# NguyenLy.net
KiCad netlist of a schematic drawn in Altium Designer
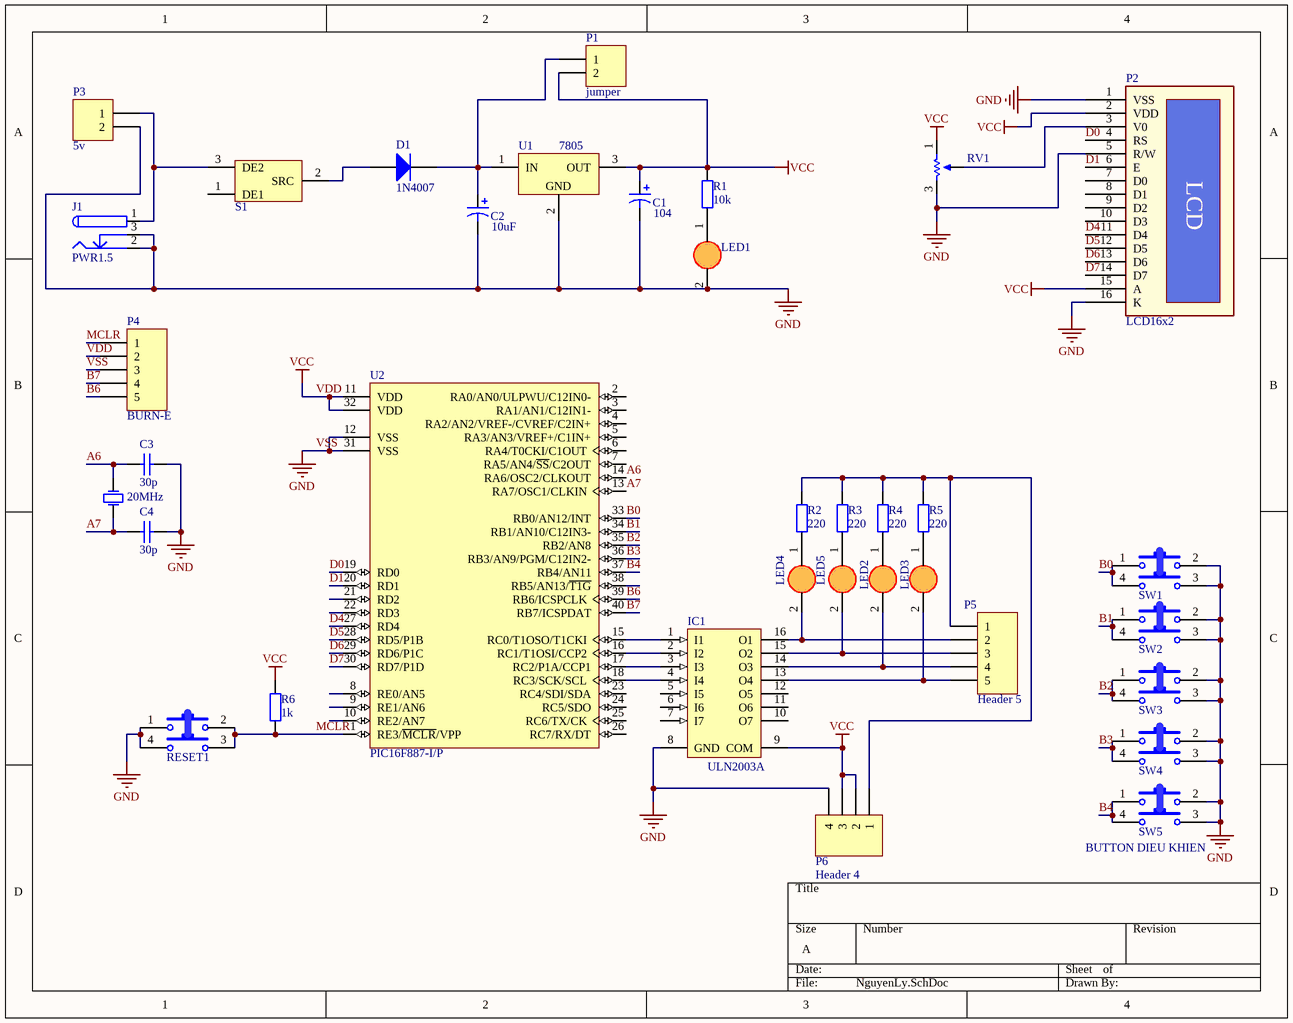
[diagram p0: NguyenLy.SchDoc]

(export (version "E")
  (design (tool "Eeschema 10.0.6"))
  (components
    (comp (ref "C1")
      (value "104")
      (footprint "C3MM")
      (description "Polarized Capacitor (Axial)")
      (fields (field (name "PUBLISHER") "Altium Limited"))
      (libsource (lib "NBBLib 14-03-2012") (part "Cap Pol 3mm"))
    )
    (comp (ref "C2")
      (value "10uF")
      (footprint "C3MM")
      (description "Polarized Capacitor (Axial)")
      (fields (field (name "PUBLISHER") "Altium Limited"))
      (libsource (lib "NBBLib 14-03-2012") (part "Cap Pol 3mm"))
    )
    (comp (ref "C3")
      (value "30p")
      (footprint "Tu-ceramic")
      (description "Capacitor")
      (fields (field (name "Comment") "Capacitor Ceramic") (field (name "PUBLISHER") "Altium Limited"))
      (libsource (lib "NBBLib 14-03-2012") (part "CapDecop"))
    )
    (comp (ref "C4")
      (value "30p")
      (footprint "Tu-ceramic")
      (description "Capacitor")
      (fields (field (name "Comment") "Capacitor Ceramic") (field (name "PUBLISHER") "Altium Limited"))
      (libsource (lib "NBBLib 14-03-2012") (part "CapDecop"))
    )
    (comp (ref "D1")
      (value "1N4007")
      (footprint "DIODE/POW/1A")
      (description "Diode Power")
      (fields (field (name "PUBLISHER") "Altium Limited"))
      (libsource (lib "NBBLib 14-03-2012") (part "Diode Power"))
    )
    (comp (ref "IC1")
      (value "ULN2003A")
      (footprint "DIP16/W0.3")
      (description "High-Voltage, High-Current Darlington Array")
      (fields (field (name "PUBLISHER") "Altium Limited"))
      (libsource (lib "syhaunguyen") (part "ULN2003A"))
    )
    (comp (ref "J1")
      (value "PWR1.5")
      (footprint "PW-J-1MM")
      (description "Low Voltage Power Supply Connector")
      (fields (field (name "PUBLISHER") "Altium Limited"))
      (libsource (lib "NBBLib 14-03-2012") (part "PWR1.5"))
    )
    (comp (ref "LED1")
      (value "LED5")
      (footprint "LED5MM")
      (description "LED 5mm")
      (libsource (lib "NBBLib 14-03-2012") (part "LED 5mm"))
    )
    (comp (ref "LED2")
      (value "LED5")
      (footprint "LED5MM")
      (description "LED 5mm")
      (libsource (lib "NBBLib 14-03-2012") (part "LED 5mm"))
    )
    (comp (ref "LED3")
      (value "LED5")
      (footprint "LED5MM")
      (description "LED 5mm")
      (libsource (lib "NBBLib 14-03-2012") (part "LED 5mm"))
    )
    (comp (ref "LED4")
      (value "LED5")
      (footprint "LED5MM")
      (description "LED 5mm")
      (libsource (lib "NBBLib 14-03-2012") (part "LED 5mm"))
    )
    (comp (ref "LED5")
      (value "LED5")
      (footprint "LED5MM")
      (description "LED 5mm")
      (libsource (lib "NBBLib 14-03-2012") (part "LED 5mm"))
    )
    (comp (ref "P1")
      (value "jumper")
      (footprint "HDR1X2")
      (description "Header, 2-Pin")
      (fields (field (name "PUBLISHER") "Altium Limited"))
      (libsource (lib "NBBLib 14-03-2012") (part "Header 2"))
    )
    (comp (ref "P2")
      (value "LCD16x2")
      (footprint "HDR1X16")
      (libsource (lib "NBBLib 14-03-2012") (part "LCD Text"))
    )
    (comp (ref "P3")
      (value "5v")
      (footprint "HDR1X2")
      (description "Header, 2-Pin")
      (fields (field (name "PUBLISHER") "Altium Limited"))
      (libsource (lib "") (part "Header 2_1"))
    )
    (comp (ref "P4")
      (value "BURN-E")
      (footprint "HDR1X5")
      (description "Header, 5-Pin")
      (fields (field (name "PUBLISHER") "Altium Limited"))
      (libsource (lib "NBBLib 14-03-2012") (part "Header 5"))
    )
    (comp (ref "P5")
      (value "Header 5")
      (footprint "HDR1X5")
      (description "Header, 5-Pin")
      (fields (field (name "PUBLISHER") "Altium Limited"))
      (libsource (lib "NBBLib 14-03-2012") (part "Header 5"))
    )
    (comp (ref "P6")
      (value "Header 4")
      (footprint "HDR1X4")
      (description "Header, 4-Pin")
      (fields (field (name "PUBLISHER") "Altium Limited"))
      (libsource (lib "NBBLib 14-03-2012") (part "Header 4"))
    )
    (comp (ref "R1")
      (value "10k")
      (footprint "DIEN TRO 1/4 W")
      (description "Resistor")
      (fields (field (name "Comment") "R0.4W") (field (name "PUBLISHER") "Altium Limited"))
      (libsource (lib "NBBLib 14-03-2012") (part "Res 1/4 W"))
    )
    (comp (ref "R2")
      (value "220")
      (footprint "DIEN TRO 1/4 W")
      (description "Resistor")
      (fields (field (name "Comment") "R0.4W") (field (name "PUBLISHER") "Altium Limited"))
      (libsource (lib "NBBLib 14-03-2012") (part "Res 1/4 W"))
    )
    (comp (ref "R3")
      (value "220")
      (footprint "DIEN TRO 1/4 W")
      (description "Resistor")
      (fields (field (name "Comment") "R0.4W") (field (name "PUBLISHER") "Altium Limited"))
      (libsource (lib "NBBLib 14-03-2012") (part "Res 1/4 W"))
    )
    (comp (ref "R4")
      (value "220")
      (footprint "DIEN TRO 1/4 W")
      (description "Resistor")
      (fields (field (name "Comment") "R0.4W") (field (name "PUBLISHER") "Altium Limited"))
      (libsource (lib "NBBLib 14-03-2012") (part "Res 1/4 W"))
    )
    (comp (ref "R5")
      (value "220")
      (footprint "DIEN TRO 1/4 W")
      (description "Resistor")
      (fields (field (name "Comment") "R0.4W") (field (name "PUBLISHER") "Altium Limited"))
      (libsource (lib "NBBLib 14-03-2012") (part "Res 1/4 W"))
    )
    (comp (ref "R6")
      (value "1k")
      (footprint "DIEN TRO 1/4 W")
      (description "Resistor")
      (fields (field (name "Comment") "R0.4W") (field (name "PUBLISHER") "Altium Limited"))
      (libsource (lib "") (part "Res 1/4 W_1"))
    )
    (comp (ref "RESET1")
      (value "SW-4P-S")
      (footprint "SW-4P-S")
      (description "Switch Small 4 Pin")
      (fields (field (name "PUBLISHER") "Altium Limited"))
      (libsource (lib "NBBLib 14-03-2012") (part "SW-4PIN-SMALL"))
    )
    (comp (ref "RV1")
      (value "RV20K")
      (footprint "RVAR10K")
      (description "Variable Resistor")
      (fields (field (name "PUBLISHER") "Altium Limited"))
      (libsource (lib "NBBLib 14-03-2012") (part "Variable Resistor"))
    )
    (comp (ref "S1")
      (value "Switch")
      (footprint "Switch")
      (libsource (lib "NBBLib 14-03-2012") (part "Switch"))
    )
    (comp (ref "SW1")
      (value "SW-4P-S")
      (footprint "SW-4P-S")
      (description "Switch Small 4 Pin")
      (fields (field (name "PUBLISHER") "Altium Limited"))
      (libsource (lib "NBBLib 14-03-2012") (part "SW-4PIN-SMALL"))
    )
    (comp (ref "SW2")
      (value "SW-4P-S")
      (footprint "SW-4P-S")
      (description "Switch Small 4 Pin")
      (fields (field (name "PUBLISHER") "Altium Limited"))
      (libsource (lib "NBBLib 14-03-2012") (part "SW-4PIN-SMALL"))
    )
    (comp (ref "SW3")
      (value "SW-4P-S")
      (footprint "SW-4P-S")
      (description "Switch Small 4 Pin")
      (fields (field (name "PUBLISHER") "Altium Limited"))
      (libsource (lib "NBBLib 14-03-2012") (part "SW-4PIN-SMALL"))
    )
    (comp (ref "SW4")
      (value "SW-4P-S")
      (footprint "SW-4P-S")
      (description "Switch Small 4 Pin")
      (fields (field (name "PUBLISHER") "Altium Limited"))
      (libsource (lib "NBBLib 14-03-2012") (part "SW-4PIN-SMALL"))
    )
    (comp (ref "SW5")
      (value "SW-4P-S")
      (footprint "SW-4P-S")
      (description "Switch Small 4 Pin")
      (fields (field (name "PUBLISHER") "Altium Limited"))
      (libsource (lib "NBBLib 14-03-2012") (part "SW-4PIN-SMALL"))
    )
    (comp (ref "U1")
      (value "7805")
      (footprint "HDR1x3 BIG")
      (description "Positive Voltage Regulator")
      (fields (field (name "PUBLISHER") "Altium Limited"))
      (libsource (lib "NBBLib 14-03-2012") (part "7809"))
    )
    (comp (ref "U2")
      (value "PIC16F887-I/P")
      (footprint "PDIP600-P40")
      (fields (field (name "PUBLISHER") "Altium Limited"))
      (libsource (lib "Microchip Microcontroller 8-Bit PIC16") (part "PIC16F887-I/P"))
    )
    (comp (ref "Y1")
      (value "20MHz")
      (footprint "XTAL")
      (description "Crystal Oscillator")
      (fields (field (name "PUBLISHER") "Altium Limited"))
      (libsource (lib "NBBLib 14-03-2012") (part "XTAL"))
    )
  )
  (nets
    (net (code "1") (name "/A6") (class "Default")
      (node (ref "C3") (pin "1") (pinfunction "1_1") (pintype "passive"))
      (node (ref "U2") (pin "14") (pinfunction "RA6/OSC2/CLKOUT_14") (pintype "bidirectional"))
      (node (ref "Y1") (pin "2") (pinfunction "OSC2_2") (pintype "passive"))
    )
    (net (code "2") (name "/A7") (class "Default")
      (node (ref "C4") (pin "1") (pinfunction "1_1") (pintype "passive"))
      (node (ref "U2") (pin "13") (pinfunction "RA7/OSC1/CLKIN_13") (pintype "bidirectional"))
      (node (ref "Y1") (pin "1") (pinfunction "OSC1_1") (pintype "passive"))
    )
    (net (code "3") (name "/B0") (class "Default")
      (node (ref "SW1") (pin "1") (pinfunction "1_1") (pintype "passive"))
      (node (ref "SW1") (pin "4") (pinfunction "4_4") (pintype "passive"))
      (node (ref "U2") (pin "33") (pinfunction "RB0/AN12/INT_33") (pintype "bidirectional"))
    )
    (net (code "4") (name "/B1") (class "Default")
      (node (ref "SW2") (pin "1") (pinfunction "1_1") (pintype "passive"))
      (node (ref "SW2") (pin "4") (pinfunction "4_4") (pintype "passive"))
      (node (ref "U2") (pin "34") (pinfunction "RB1/AN10/C12IN3-_34") (pintype "bidirectional"))
    )
    (net (code "5") (name "/B2") (class "Default")
      (node (ref "SW3") (pin "1") (pinfunction "1_1") (pintype "passive"))
      (node (ref "SW3") (pin "4") (pinfunction "4_4") (pintype "passive"))
      (node (ref "U2") (pin "35") (pinfunction "RB2/AN8_35") (pintype "bidirectional"))
    )
    (net (code "6") (name "/B3") (class "Default")
      (node (ref "SW4") (pin "1") (pinfunction "1_1") (pintype "passive"))
      (node (ref "SW4") (pin "4") (pinfunction "4_4") (pintype "passive"))
      (node (ref "U2") (pin "36") (pinfunction "RB3/AN9/PGM/C12IN2-_36") (pintype "bidirectional"))
    )
    (net (code "7") (name "/B4") (class "Default")
      (node (ref "SW5") (pin "1") (pinfunction "1_1") (pintype "passive"))
      (node (ref "SW5") (pin "4") (pinfunction "4_4") (pintype "passive"))
      (node (ref "U2") (pin "37") (pinfunction "RB4/AN11_37") (pintype "bidirectional"))
    )
    (net (code "8") (name "/B6") (class "Default")
      (node (ref "P4") (pin "5") (pinfunction "5_5") (pintype "passive"))
      (node (ref "U2") (pin "39") (pinfunction "RB6/ICSPCLK_39") (pintype "bidirectional"))
    )
    (net (code "9") (name "/B7") (class "Default")
      (node (ref "P4") (pin "4") (pinfunction "4_4") (pintype "passive"))
      (node (ref "U2") (pin "40") (pinfunction "RB7/ICSPDAT_40") (pintype "bidirectional"))
    )
    (net (code "10") (name "/D0") (class "Default")
      (node (ref "P2") (pin "4") (pinfunction "RS_4") (pintype "passive"))
      (node (ref "U2") (pin "19") (pinfunction "RD0_19") (pintype "bidirectional"))
    )
    (net (code "11") (name "/D1") (class "Default")
      (node (ref "P2") (pin "6") (pinfunction "E_6") (pintype "passive"))
      (node (ref "U2") (pin "20") (pinfunction "RD1_20") (pintype "bidirectional"))
    )
    (net (code "12") (name "/D4") (class "Default")
      (node (ref "P2") (pin "11") (pinfunction "D4_11") (pintype "passive"))
      (node (ref "U2") (pin "27") (pinfunction "RD4_27") (pintype "bidirectional"))
    )
    (net (code "13") (name "/D5") (class "Default")
      (node (ref "P2") (pin "12") (pinfunction "D5_12") (pintype "passive"))
      (node (ref "U2") (pin "28") (pinfunction "RD5/P1B_28") (pintype "bidirectional"))
    )
    (net (code "14") (name "/D6") (class "Default")
      (node (ref "P2") (pin "13") (pinfunction "D6_13") (pintype "passive"))
      (node (ref "U2") (pin "29") (pinfunction "RD6/P1C_29") (pintype "bidirectional"))
    )
    (net (code "15") (name "/D7") (class "Default")
      (node (ref "P2") (pin "14") (pinfunction "D7_14") (pintype "passive"))
      (node (ref "U2") (pin "30") (pinfunction "RD7/P1D_30") (pintype "bidirectional"))
    )
    (net (code "16") (name "/MCLR") (class "Default")
      (node (ref "P4") (pin "1") (pinfunction "1_1") (pintype "passive"))
      (node (ref "R6") (pin "2") (pinfunction "2_2") (pintype "passive"))
      (node (ref "RESET1") (pin "2") (pinfunction "2_2") (pintype "passive"))
      (node (ref "RESET1") (pin "3") (pinfunction "3_3") (pintype "passive"))
      (node (ref "U2") (pin "1") (pinfunction "RE3/~{MCLR}/VPP_1") (pintype "bidirectional"))
    )
    (net (code "17") (name "GND") (class "Default")
      (node (ref "C1") (pin "2") (pinfunction "2_2") (pintype "passive"))
      (node (ref "C2") (pin "2") (pinfunction "2_2") (pintype "passive"))
      (node (ref "C3") (pin "2") (pinfunction "2_2") (pintype "passive"))
      (node (ref "C4") (pin "2") (pinfunction "2_2") (pintype "passive"))
      (node (ref "IC1") (pin "8") (pinfunction "GND_8") (pintype "power_in"))
      (node (ref "J1") (pin "2") (pinfunction "2_2") (pintype "power_in"))
      (node (ref "J1") (pin "3") (pinfunction "3_3") (pintype "power_in"))
      (node (ref "LED1") (pin "2") (pinfunction "K_2") (pintype "passive"))
      (node (ref "P2") (pin "1") (pinfunction "VSS_1") (pintype "passive"))
      (node (ref "P2") (pin "16") (pinfunction "K_16") (pintype "passive"))
      (node (ref "P2") (pin "5") (pinfunction "R/W_5") (pintype "passive"))
      (node (ref "P3") (pin "2") (pinfunction "2_2") (pintype "passive"))
      (node (ref "P4") (pin "3") (pinfunction "3_3") (pintype "passive"))
      (node (ref "P6") (pin "4") (pinfunction "4_4") (pintype "passive"))
      (node (ref "RESET1") (pin "1") (pinfunction "1_1") (pintype "passive"))
      (node (ref "RESET1") (pin "4") (pinfunction "4_4") (pintype "passive"))
      (node (ref "RV1") (pin "3") (pinfunction "3_3") (pintype "passive"))
      (node (ref "SW1") (pin "2") (pinfunction "2_2") (pintype "passive"))
      (node (ref "SW1") (pin "3") (pinfunction "3_3") (pintype "passive"))
      (node (ref "SW2") (pin "2") (pinfunction "2_2") (pintype "passive"))
      (node (ref "SW2") (pin "3") (pinfunction "3_3") (pintype "passive"))
      (node (ref "SW3") (pin "2") (pinfunction "2_2") (pintype "passive"))
      (node (ref "SW3") (pin "3") (pinfunction "3_3") (pintype "passive"))
      (node (ref "SW4") (pin "2") (pinfunction "2_2") (pintype "passive"))
      (node (ref "SW4") (pin "3") (pinfunction "3_3") (pintype "passive"))
      (node (ref "SW5") (pin "2") (pinfunction "2_2") (pintype "passive"))
      (node (ref "SW5") (pin "3") (pinfunction "3_3") (pintype "passive"))
      (node (ref "U1") (pin "2") (pinfunction "GND_2") (pintype "power_in"))
      (node (ref "U2") (pin "12") (pinfunction "VSS_12") (pintype "power_in"))
      (node (ref "U2") (pin "31") (pinfunction "VSS_31") (pintype "power_in"))
    )
    (net (code "18") (name "Net-(D1-A)") (class "Default")
      (node (ref "D1") (pin "1") (pinfunction "A_1") (pintype "passive"))
      (node (ref "S1") (pin "2") (pinfunction "SRC_2") (pintype "passive"))
    )
    (net (code "19") (name "Net-(D1-K)") (class "Default")
      (node (ref "C2") (pin "1") (pinfunction "1_1") (pintype "passive"))
      (node (ref "D1") (pin "2") (pinfunction "K_2") (pintype "passive"))
      (node (ref "P1") (pin "1") (pinfunction "1_1") (pintype "passive"))
      (node (ref "U1") (pin "1") (pinfunction "IN_1") (pintype "power_in"))
    )
    (net (code "20") (name "Net-(IC1-I1)") (class "Default")
      (node (ref "IC1") (pin "1") (pinfunction "I1_1") (pintype "input"))
      (node (ref "U2") (pin "15") (pinfunction "RC0/T1OSO/T1CKI_15") (pintype "bidirectional"))
    )
    (net (code "21") (name "Net-(IC1-I2)") (class "Default")
      (node (ref "IC1") (pin "2") (pinfunction "I2_2") (pintype "input"))
      (node (ref "U2") (pin "16") (pinfunction "RC1/T1OSI/CCP2_16") (pintype "bidirectional"))
    )
    (net (code "22") (name "Net-(IC1-I3)") (class "Default")
      (node (ref "IC1") (pin "3") (pinfunction "I3_3") (pintype "input"))
      (node (ref "U2") (pin "17") (pinfunction "RC2/P1A/CCP1_17") (pintype "bidirectional"))
    )
    (net (code "23") (name "Net-(IC1-I4)") (class "Default")
      (node (ref "IC1") (pin "4") (pinfunction "I4_4") (pintype "input"))
      (node (ref "U2") (pin "18") (pinfunction "RC3/SCK/SCL_18") (pintype "bidirectional"))
    )
    (net (code "24") (name "Net-(IC1-O1)") (class "Default")
      (node (ref "IC1") (pin "16") (pinfunction "O1_16") (pintype "open_collector"))
      (node (ref "LED4") (pin "2") (pinfunction "K_2") (pintype "passive"))
      (node (ref "P5") (pin "2") (pinfunction "2_2") (pintype "passive"))
    )
    (net (code "25") (name "Net-(IC1-O2)") (class "Default")
      (node (ref "IC1") (pin "15") (pinfunction "O2_15") (pintype "open_collector"))
      (node (ref "LED5") (pin "2") (pinfunction "K_2") (pintype "passive"))
      (node (ref "P5") (pin "3") (pinfunction "3_3") (pintype "passive"))
    )
    (net (code "26") (name "Net-(IC1-O3)") (class "Default")
      (node (ref "IC1") (pin "14") (pinfunction "O3_14") (pintype "open_collector"))
      (node (ref "LED2") (pin "2") (pinfunction "K_2") (pintype "passive"))
      (node (ref "P5") (pin "4") (pinfunction "4_4") (pintype "passive"))
    )
    (net (code "27") (name "Net-(IC1-O4)") (class "Default")
      (node (ref "IC1") (pin "13") (pinfunction "O4_13") (pintype "open_collector"))
      (node (ref "LED3") (pin "2") (pinfunction "K_2") (pintype "passive"))
      (node (ref "P5") (pin "5") (pinfunction "5_5") (pintype "passive"))
    )
    (net (code "28") (name "Net-(LED1-A)") (class "Default")
      (node (ref "LED1") (pin "1") (pinfunction "A_1") (pintype "passive"))
      (node (ref "R1") (pin "1") (pinfunction "1_1") (pintype "passive"))
    )
    (net (code "29") (name "Net-(LED2-A)") (class "Default")
      (node (ref "LED2") (pin "1") (pinfunction "A_1") (pintype "passive"))
      (node (ref "R4") (pin "1") (pinfunction "1_1") (pintype "passive"))
    )
    (net (code "30") (name "Net-(LED3-A)") (class "Default")
      (node (ref "LED3") (pin "1") (pinfunction "A_1") (pintype "passive"))
      (node (ref "R5") (pin "1") (pinfunction "1_1") (pintype "passive"))
    )
    (net (code "31") (name "Net-(LED4-A)") (class "Default")
      (node (ref "LED4") (pin "1") (pinfunction "A_1") (pintype "passive"))
      (node (ref "R2") (pin "1") (pinfunction "1_1") (pintype "passive"))
    )
    (net (code "32") (name "Net-(LED5-A)") (class "Default")
      (node (ref "LED5") (pin "1") (pinfunction "A_1") (pintype "passive"))
      (node (ref "R3") (pin "1") (pinfunction "1_1") (pintype "passive"))
    )
    (net (code "33") (name "Net-(P2-V0)") (class "Default")
      (node (ref "P2") (pin "3") (pinfunction "V0_3") (pintype "passive"))
      (node (ref "RV1") (pin "2") (pinfunction "2_2") (pintype "passive"))
    )
    (net (code "34") (name "Net-(P5-Pad1)") (class "Default")
      (node (ref "P5") (pin "1") (pinfunction "1_1") (pintype "passive"))
      (node (ref "P6") (pin "1") (pinfunction "1_1") (pintype "passive"))
      (node (ref "R2") (pin "2") (pinfunction "2_2") (pintype "passive"))
      (node (ref "R3") (pin "2") (pinfunction "2_2") (pintype "passive"))
      (node (ref "R4") (pin "2") (pinfunction "2_2") (pintype "passive"))
      (node (ref "R5") (pin "2") (pinfunction "2_2") (pintype "passive"))
    )
    (net (code "35") (name "Net-(S1-DE2)") (class "Default")
      (node (ref "J1") (pin "1") (pinfunction "1_1") (pintype "power_in"))
      (node (ref "P3") (pin "1") (pinfunction "1_1") (pintype "passive"))
      (node (ref "S1") (pin "3") (pinfunction "DE2_3") (pintype "passive"))
    )
    (net (code "36") (name "VCC") (class "Default")
      (node (ref "C1") (pin "1") (pinfunction "1_1") (pintype "passive"))
      (node (ref "IC1") (pin "9") (pinfunction "COM_9") (pintype "passive"))
      (node (ref "P1") (pin "2") (pinfunction "2_2") (pintype "passive"))
      (node (ref "P2") (pin "15") (pinfunction "A_15") (pintype "passive"))
      (node (ref "P2") (pin "2") (pinfunction "VDD_2") (pintype "passive"))
      (node (ref "P4") (pin "2") (pinfunction "2_2") (pintype "passive"))
      (node (ref "P6") (pin "2") (pinfunction "2_2") (pintype "passive"))
      (node (ref "P6") (pin "3") (pinfunction "3_3") (pintype "passive"))
      (node (ref "R1") (pin "2") (pinfunction "2_2") (pintype "passive"))
      (node (ref "R6") (pin "1") (pinfunction "1_1") (pintype "passive"))
      (node (ref "RV1") (pin "1") (pinfunction "1_1") (pintype "passive"))
      (node (ref "U1") (pin "3") (pinfunction "OUT_3") (pintype "power_in"))
      (node (ref "U2") (pin "11") (pinfunction "VDD_11") (pintype "power_in"))
      (node (ref "U2") (pin "32") (pinfunction "VDD_32") (pintype "power_in"))
    )
    (net (code "37") (name "unconnected-(IC1-I5-Pad5)") (class "Default")
      (node (ref "IC1") (pin "5") (pinfunction "I5_5") (pintype "input"))
    )
    (net (code "38") (name "unconnected-(IC1-I6-Pad6)") (class "Default")
      (node (ref "IC1") (pin "6") (pinfunction "I6_6") (pintype "input"))
    )
    (net (code "39") (name "unconnected-(IC1-I7-Pad7)") (class "Default")
      (node (ref "IC1") (pin "7") (pinfunction "I7_7") (pintype "input"))
    )
    (net (code "40") (name "unconnected-(IC1-O5-Pad12)") (class "Default")
      (node (ref "IC1") (pin "12") (pinfunction "O5_12") (pintype "open_collector"))
    )
    (net (code "41") (name "unconnected-(IC1-O6-Pad11)") (class "Default")
      (node (ref "IC1") (pin "11") (pinfunction "O6_11") (pintype "open_collector"))
    )
    (net (code "42") (name "unconnected-(IC1-O7-Pad10)") (class "Default")
      (node (ref "IC1") (pin "10") (pinfunction "O7_10") (pintype "open_collector"))
    )
    (net (code "43") (name "unconnected-(P2-D0-Pad7)") (class "Default")
      (node (ref "P2") (pin "7") (pinfunction "D0_7") (pintype "passive"))
    )
    (net (code "44") (name "unconnected-(P2-D1-Pad8)") (class "Default")
      (node (ref "P2") (pin "8") (pinfunction "D1_8") (pintype "passive"))
    )
    (net (code "45") (name "unconnected-(P2-D2-Pad9)") (class "Default")
      (node (ref "P2") (pin "9") (pinfunction "D2_9") (pintype "passive"))
    )
    (net (code "46") (name "unconnected-(P2-D3-Pad10)") (class "Default")
      (node (ref "P2") (pin "10") (pinfunction "D3_10") (pintype "passive"))
    )
    (net (code "47") (name "unconnected-(S1-DE1-Pad1)") (class "Default")
      (node (ref "S1") (pin "1") (pinfunction "DE1_1") (pintype "passive"))
    )
    (net (code "48") (name "unconnected-(S1-Pad4)") (class "Default")
      (node (ref "S1") (pin "4") (pinfunction "4_4") (pintype "passive"))
    )
    (net (code "49") (name "unconnected-(S1-Pad5)") (class "Default")
      (node (ref "S1") (pin "5") (pinfunction "5_5") (pintype "passive"))
    )
    (net (code "50") (name "unconnected-(U2-RA0{slash}AN0{slash}ULPWU{slash}C12IN0--Pad2)") (class "Default")
      (node (ref "U2") (pin "2") (pinfunction "RA0/AN0/ULPWU/C12IN0-_2") (pintype "bidirectional"))
    )
    (net (code "51") (name "unconnected-(U2-RA1{slash}AN1{slash}C12IN1--Pad3)") (class "Default")
      (node (ref "U2") (pin "3") (pinfunction "RA1/AN1/C12IN1-_3") (pintype "bidirectional"))
    )
    (net (code "52") (name "unconnected-(U2-RA2{slash}AN2{slash}VREF-{slash}CVREF{slash}C2IN+-Pad4)") (class "Default")
      (node (ref "U2") (pin "4") (pinfunction "RA2/AN2/VREF-/CVREF/C2IN+_4") (pintype "bidirectional"))
    )
    (net (code "53") (name "unconnected-(U2-RA3{slash}AN3{slash}VREF+{slash}C1IN+-Pad5)") (class "Default")
      (node (ref "U2") (pin "5") (pinfunction "RA3/AN3/VREF+/C1IN+_5") (pintype "bidirectional"))
    )
    (net (code "54") (name "unconnected-(U2-RA4{slash}T0CKI{slash}C1OUT-Pad6)") (class "Default")
      (node (ref "U2") (pin "6") (pinfunction "RA4/T0CKI/C1OUT_6") (pintype "bidirectional"))
    )
    (net (code "55") (name "unconnected-(U2-RA5{slash}AN4{slash}~{SS}{slash}C2OUT-Pad7)") (class "Default")
      (node (ref "U2") (pin "7") (pinfunction "RA5/AN4/~{SS}/C2OUT_7") (pintype "bidirectional"))
    )
    (net (code "56") (name "unconnected-(U2-RB5{slash}AN13{slash}~{T1G}-Pad38)") (class "Default")
      (node (ref "U2") (pin "38") (pinfunction "RB5/AN13/~{T1G}_38") (pintype "bidirectional"))
    )
    (net (code "57") (name "unconnected-(U2-RC4{slash}SDI{slash}SDA-Pad23)") (class "Default")
      (node (ref "U2") (pin "23") (pinfunction "RC4/SDI/SDA_23") (pintype "bidirectional"))
    )
    (net (code "58") (name "unconnected-(U2-RC5{slash}SDO-Pad24)") (class "Default")
      (node (ref "U2") (pin "24") (pinfunction "RC5/SDO_24") (pintype "bidirectional"))
    )
    (net (code "59") (name "unconnected-(U2-RC6{slash}TX{slash}CK-Pad25)") (class "Default")
      (node (ref "U2") (pin "25") (pinfunction "RC6/TX/CK_25") (pintype "bidirectional"))
    )
    (net (code "60") (name "unconnected-(U2-RC7{slash}RX{slash}DT-Pad26)") (class "Default")
      (node (ref "U2") (pin "26") (pinfunction "RC7/RX/DT_26") (pintype "bidirectional"))
    )
    (net (code "61") (name "unconnected-(U2-RD2-Pad21)") (class "Default")
      (node (ref "U2") (pin "21") (pinfunction "RD2_21") (pintype "bidirectional"))
    )
    (net (code "62") (name "unconnected-(U2-RD3-Pad22)") (class "Default")
      (node (ref "U2") (pin "22") (pinfunction "RD3_22") (pintype "bidirectional"))
    )
    (net (code "63") (name "unconnected-(U2-RE0{slash}AN5-Pad8)") (class "Default")
      (node (ref "U2") (pin "8") (pinfunction "RE0/AN5_8") (pintype "bidirectional"))
    )
    (net (code "64") (name "unconnected-(U2-RE1{slash}AN6-Pad9)") (class "Default")
      (node (ref "U2") (pin "9") (pinfunction "RE1/AN6_9") (pintype "bidirectional"))
    )
    (net (code "65") (name "unconnected-(U2-RE2{slash}AN7-Pad10)") (class "Default")
      (node (ref "U2") (pin "10") (pinfunction "RE2/AN7_10") (pintype "bidirectional"))
    )
  )
)
